# mybiosphere_output_board.net
KiCad netlist of a schematic drawn in EAGLE
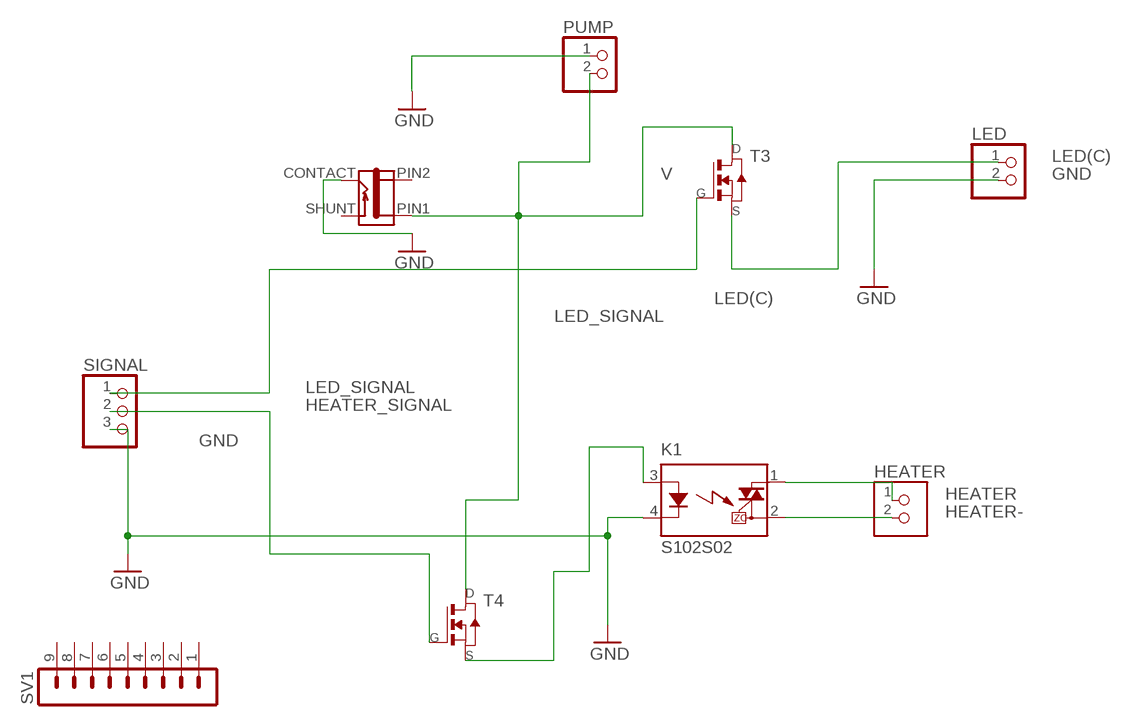
[diagram p0: schematic, sheet 1]

(export (version "E")
  (design (tool "Eeschema 10.0.6"))
  (components
    (comp (ref "HEATER")
      (value "TERM-1X02-FABLAB")
      (footprint "eagle-import:ED555DS-2DS")
      (libsource (lib "eagle-import") (part "TERM-1X02-FABLAB"))
    )
    (comp (ref "J1")
      (value "JACK-2.1MM")
      (footprint "eagle-import:PJ-002AH-SMT")
      (libsource (lib "eagle-import") (part "JACK-2.1MM"))
    )
    (comp (ref "K1")
      (value "S102S02")
      (footprint "eagle-import:S202S02")
      (libsource (lib "eagle-import") (part "S02S021"))
    )
    (comp (ref "LED")
      (value "PINHD-1X2/90")
      (footprint "eagle-import:1X02_90")
      (libsource (lib "eagle-import") (part "PINHD-1X2/90"))
    )
    (comp (ref "PUMP")
      (value "PINHD-1X2/90")
      (footprint "eagle-import:1X02_90")
      (libsource (lib "eagle-import") (part "PINHD-1X2/90"))
    )
    (comp (ref "SIGNAL")
      (value "PINHD-1X3")
      (footprint "eagle-import:1X03")
      (libsource (lib "eagle-import") (part "PINHD-1X3"))
    )
    (comp (ref "SV1")
      (value "MA09-1")
      (footprint "eagle-import:MA09-1")
      (libsource (lib "eagle-import") (part "MA09-1"))
    )
    (comp (ref "T3")
      (value "NMOSFETTO252")
      (footprint "eagle-import:TO252")
      (libsource (lib "eagle-import") (part "NMOSFETTO252"))
    )
    (comp (ref "T4")
      (value "NMOSFETTO252")
      (footprint "eagle-import:TO252")
      (libsource (lib "eagle-import") (part "NMOSFETTO252"))
    )
  )
  (nets
    (net (code "1") (name "/HEATER") (class "Default")
      (node (ref "HEATER") (pin "1") (pinfunction "1_1") (pintype "passive"))
      (node (ref "K1") (pin "1") (pinfunction "DS1_1") (pintype "passive"))
    )
    (net (code "2") (name "/HEATER-") (class "Default")
      (node (ref "HEATER") (pin "2") (pinfunction "2_2") (pintype "passive"))
      (node (ref "K1") (pin "2") (pinfunction "DS2_2") (pintype "passive"))
    )
    (net (code "3") (name "/HEATER_SIGNAL") (class "Default")
      (node (ref "SIGNAL") (pin "2") (pinfunction "2_2") (pintype "passive"))
      (node (ref "T4") (pin "1") (pinfunction "G_1") (pintype "passive"))
    )
    (net (code "4") (name "/LED(C)") (class "Default")
      (node (ref "LED") (pin "1") (pinfunction "1_1") (pintype "passive"))
      (node (ref "T3") (pin "2") (pinfunction "S_2") (pintype "passive"))
    )
    (net (code "5") (name "/LED_SIGNAL") (class "Default")
      (node (ref "SIGNAL") (pin "1") (pinfunction "1_1") (pintype "passive"))
      (node (ref "T3") (pin "1") (pinfunction "G_1") (pintype "passive"))
    )
    (net (code "6") (name "/PIN2") (class "Default")
      (node (ref "J1") (pin "PIN2") (pinfunction "PIN2_PIN2") (pintype "power_in"))
    )
    (net (code "7") (name "/SHUNT") (class "Default")
      (node (ref "J1") (pin "SHUNT") (pinfunction "SHUNT_SHUNT") (pintype "power_in"))
    )
    (net (code "8") (name "/V") (class "Default")
      (node (ref "J1") (pin "PIN1") (pinfunction "PIN1_PIN1") (pintype "power_in"))
      (node (ref "PUMP") (pin "2") (pinfunction "2_2") (pintype "passive"))
      (node (ref "T3") (pin "3") (pinfunction "D_3") (pintype "passive"))
      (node (ref "T4") (pin "3") (pinfunction "D_3") (pintype "passive"))
    )
    (net (code "9") (name "GND") (class "Default")
      (node (ref "J1") (pin "CONTACT") (pinfunction "CONTACT_CONTACT") (pintype "power_in"))
      (node (ref "K1") (pin "4") (pinfunction "K_4") (pintype "passive"))
      (node (ref "LED") (pin "2") (pinfunction "2_2") (pintype "passive"))
      (node (ref "PUMP") (pin "1") (pinfunction "1_1") (pintype "passive"))
      (node (ref "SIGNAL") (pin "3") (pinfunction "3_3") (pintype "passive"))
    )
    (net (code "10") (name "Net-(K1-A)") (class "Default")
      (node (ref "K1") (pin "3") (pinfunction "A_3") (pintype "passive"))
      (node (ref "T4") (pin "2") (pinfunction "S_2") (pintype "passive"))
    )
    (net (code "11") (name "unconnected-(SV1-Pad1)") (class "Default")
      (node (ref "SV1") (pin "1") (pinfunction "1_1") (pintype "passive"))
    )
    (net (code "12") (name "unconnected-(SV1-Pad2)") (class "Default")
      (node (ref "SV1") (pin "2") (pinfunction "2_2") (pintype "passive"))
    )
    (net (code "13") (name "unconnected-(SV1-Pad3)") (class "Default")
      (node (ref "SV1") (pin "3") (pinfunction "3_3") (pintype "passive"))
    )
    (net (code "14") (name "unconnected-(SV1-Pad4)") (class "Default")
      (node (ref "SV1") (pin "4") (pinfunction "4_4") (pintype "passive"))
    )
    (net (code "15") (name "unconnected-(SV1-Pad5)") (class "Default")
      (node (ref "SV1") (pin "5") (pinfunction "5_5") (pintype "passive"))
    )
    (net (code "16") (name "unconnected-(SV1-Pad6)") (class "Default")
      (node (ref "SV1") (pin "6") (pinfunction "6_6") (pintype "passive"))
    )
    (net (code "17") (name "unconnected-(SV1-Pad7)") (class "Default")
      (node (ref "SV1") (pin "7") (pinfunction "7_7") (pintype "passive"))
    )
    (net (code "18") (name "unconnected-(SV1-Pad8)") (class "Default")
      (node (ref "SV1") (pin "8") (pinfunction "8_8") (pintype "passive"))
    )
    (net (code "19") (name "unconnected-(SV1-Pad9)") (class "Default")
      (node (ref "SV1") (pin "9") (pinfunction "9_9") (pintype "passive"))
    )
  )
)
